# SW6208_A_C_LED__188.net
KiCad netlist of a schematic drawn in Altium Designer
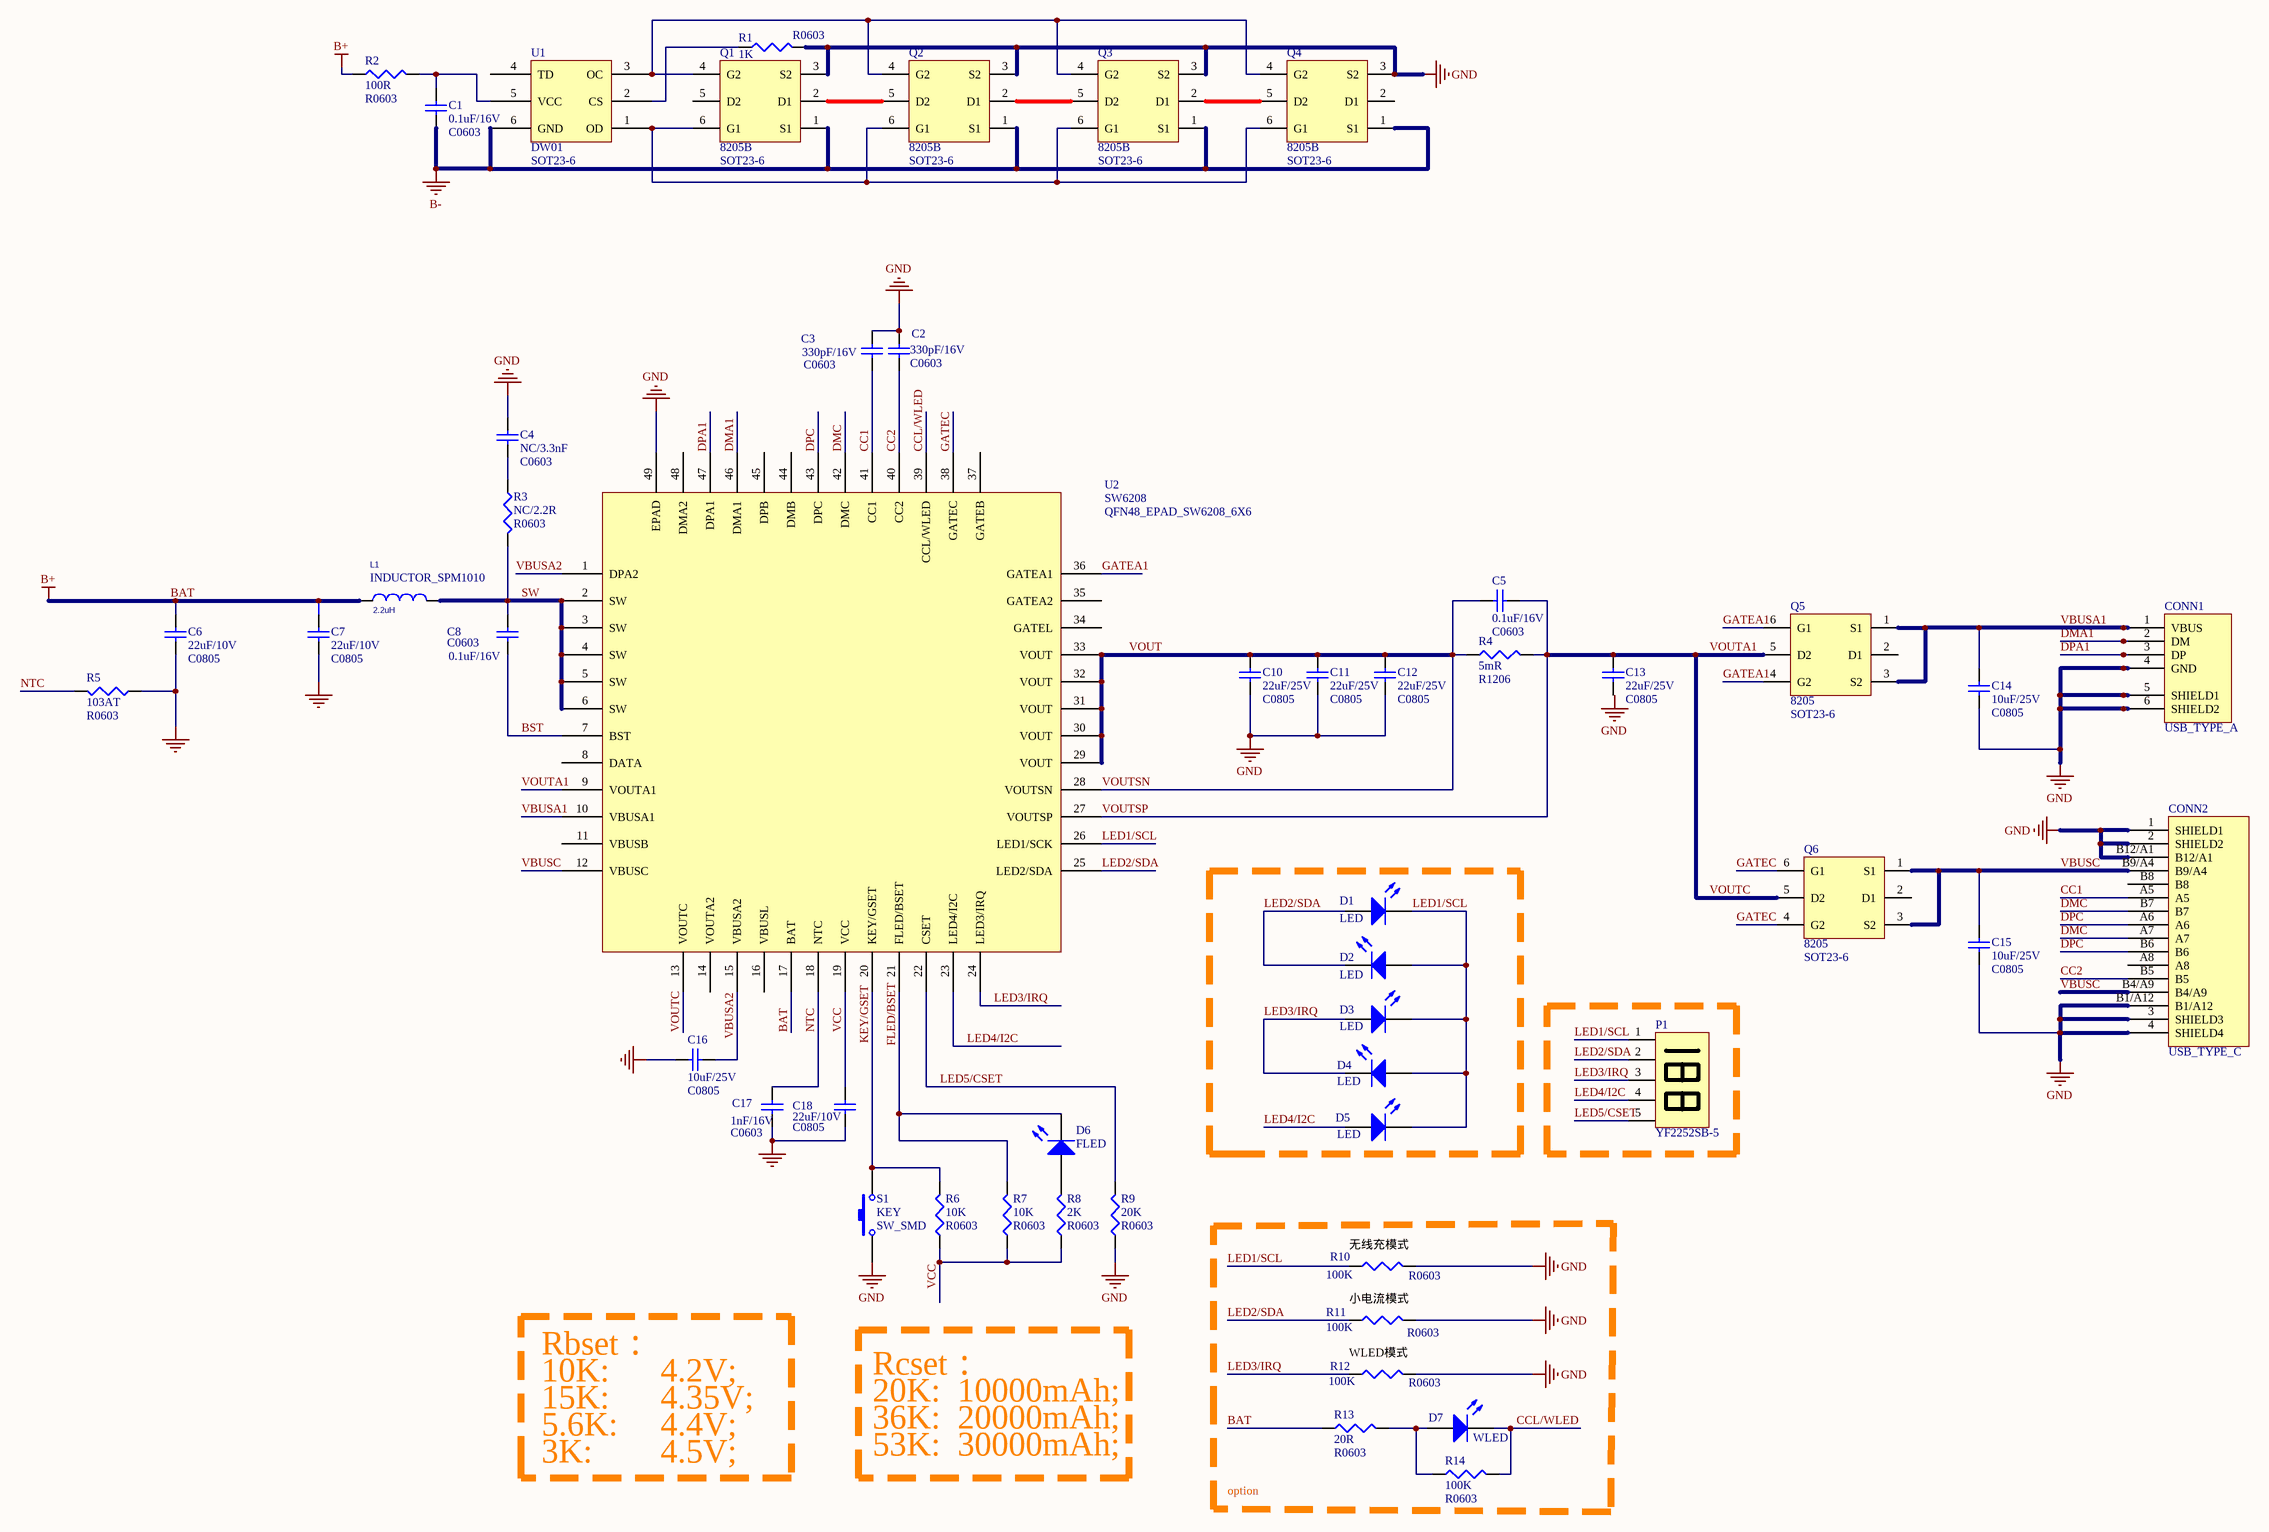
[diagram p0: SW6208+A+C+LED_普通188数码管.SchDoc]

(export (version "E")
  (design (tool "Eeschema 10.0.6"))
  (components
    (comp (ref "C1")
      (value "0.1uF/16V")
      (footprint "C0603")
      (description "Capacitor")
      (fields (field (name "PUBLISHER") "Altium Limited"))
      (libsource (lib "参考设计器件原理图更新") (part "CAP0603"))
    )
    (comp (ref "C2")
      (value "330pF/16V")
      (footprint "C0603")
      (description "Capacitor")
      (fields (field (name "PUBLISHER") "Altium Limited"))
      (libsource (lib "参考设计器件原理图更新") (part "CAP0603"))
    )
    (comp (ref "C3")
      (value "330pF/16V")
      (footprint "C0603")
      (description "Capacitor")
      (fields (field (name "PUBLISHER") "Altium Limited"))
      (libsource (lib "参考设计器件原理图更新") (part "CAP0603"))
    )
    (comp (ref "C4")
      (value "NC/3.3nF")
      (footprint "C0603")
      (description "Capacitor")
      (fields (field (name "PUBLISHER") "Altium Limited"))
      (libsource (lib "参考设计器件原理图更新") (part "CAP0603"))
    )
    (comp (ref "C5")
      (value "0.1uF/16V")
      (footprint "C0603")
      (description "Capacitor")
      (fields (field (name "PUBLISHER") "Altium Limited"))
      (libsource (lib "参考设计器件原理图更新") (part "CAP0603"))
    )
    (comp (ref "C6")
      (value "22uF/10V")
      (footprint "C0805")
      (description "Capacitor")
      (fields (field (name "PUBLISHER") "Altium Limited"))
      (libsource (lib "参考设计器件原理图更新") (part "CAP0805"))
    )
    (comp (ref "C7")
      (value "22uF/10V")
      (footprint "C0805")
      (description "Capacitor")
      (fields (field (name "PUBLISHER") "Altium Limited"))
      (libsource (lib "参考设计器件原理图更新") (part "CAP0805"))
    )
    (comp (ref "C8")
      (value "0.1uF/16V")
      (footprint "C0603")
      (description "Capacitor")
      (fields (field (name "PUBLISHER") "Altium Limited"))
      (libsource (lib "参考设计器件原理图更新") (part "CAP0603"))
    )
    (comp (ref "C10")
      (value "22uF/25V")
      (footprint "C0805")
      (description "Capacitor")
      (fields (field (name "PUBLISHER") "Altium Limited"))
      (libsource (lib "参考设计器件原理图更新") (part "CAP0805"))
    )
    (comp (ref "C11")
      (value "22uF/25V")
      (footprint "C0805")
      (description "Capacitor")
      (fields (field (name "PUBLISHER") "Altium Limited"))
      (libsource (lib "参考设计器件原理图更新") (part "CAP0805"))
    )
    (comp (ref "C12")
      (value "22uF/25V")
      (footprint "C0805")
      (description "Capacitor")
      (fields (field (name "PUBLISHER") "Altium Limited"))
      (libsource (lib "参考设计器件原理图更新") (part "CAP0805"))
    )
    (comp (ref "C13")
      (value "22uF/25V")
      (footprint "C0805")
      (description "Capacitor")
      (fields (field (name "PUBLISHER") "Altium Limited"))
      (libsource (lib "参考设计器件原理图更新") (part "CAP0805"))
    )
    (comp (ref "C14")
      (value "10uF/25V")
      (footprint "C0805")
      (description "Capacitor")
      (fields (field (name "PUBLISHER") "Altium Limited"))
      (libsource (lib "参考设计器件原理图更新") (part "CAP0805"))
    )
    (comp (ref "C15")
      (value "10uF/25V")
      (footprint "C0805")
      (description "Capacitor")
      (fields (field (name "PUBLISHER") "Altium Limited"))
      (libsource (lib "参考设计器件原理图更新") (part "CAP0805"))
    )
    (comp (ref "C16")
      (value "10uF/25V")
      (footprint "C0805")
      (description "Capacitor")
      (fields (field (name "PUBLISHER") "Altium Limited"))
      (libsource (lib "参考设计器件原理图更新") (part "CAP0805"))
    )
    (comp (ref "C17")
      (value "1nF/16V")
      (footprint "C0603")
      (description "Capacitor")
      (fields (field (name "PUBLISHER") "Altium Limited"))
      (libsource (lib "参考设计器件原理图更新") (part "CAP0603"))
    )
    (comp (ref "C18")
      (value "22uF/10V")
      (footprint "C0805")
      (description "Capacitor")
      (fields (field (name "PUBLISHER") "Altium Limited"))
      (libsource (lib "参考设计器件原理图更新") (part "CAP0805"))
    )
    (comp (ref "CONN1")
      (value "USB_TYPE_A")
      (footprint "USB_TYPE_A")
      (libsource (lib "参考设计器件原理图更新") (part "USB_TYPE_A"))
    )
    (comp (ref "CONN2")
      (value "USB_TYPE_C")
      (footprint "LOUISAD:USB_TYPE_C")
      (libsource (lib "参考设计器件原理图更新") (part "USB_TYPE_C"))
    )
    (comp (ref "D1")
      (value "LED")
      (footprint "LED0603")
      (fields (field (name "PUBLISHER") "Altium Limited"))
      (libsource (lib "参考设计器件原理图更新") (part "LED_0603"))
    )
    (comp (ref "D2")
      (value "LED")
      (footprint "LED0603")
      (fields (field (name "PUBLISHER") "Altium Limited"))
      (libsource (lib "参考设计器件原理图更新") (part "LED_0603"))
    )
    (comp (ref "D3")
      (value "LED")
      (footprint "LED0603")
      (fields (field (name "PUBLISHER") "Altium Limited"))
      (libsource (lib "参考设计器件原理图更新") (part "LED_0603"))
    )
    (comp (ref "D4")
      (value "LED")
      (footprint "LED0603")
      (fields (field (name "PUBLISHER") "Altium Limited"))
      (libsource (lib "参考设计器件原理图更新") (part "LED_0603"))
    )
    (comp (ref "D5")
      (value "LED")
      (footprint "LED0603")
      (fields (field (name "PUBLISHER") "Altium Limited"))
      (libsource (lib "参考设计器件原理图更新") (part "LED_0603"))
    )
    (comp (ref "D6")
      (value "FLED")
      (footprint "LED0603")
      (description "LED")
      (fields (field (name "PUBLISHER") "Altium Limited"))
      (libsource (lib "参考设计器件原理图更新") (part "LED_0603"))
    )
    (comp (ref "D7")
      (value "WLED")
      (footprint "LED_5MM")
      (fields (field (name "PUBLISHER") "Altium Limited"))
      (libsource (lib "参考设计器件原理图更新") (part "WLED"))
    )
    (comp (ref "L1")
      (value "2.2uH")
      (footprint "INDUCTOR_SPM1010")
      (description "INDUCTOR")
      (libsource (lib "参考设计器件原理图更新") (part "INDUCTOR_SPM1010"))
    )
    (comp (ref "P1")
      (value "YF2252SB-5")
      (footprint "LED_Display_5")
      (description "188_LED_Display")
      (libsource (lib "参考设计器件原理图更新") (part "LED_Display_5"))
    )
    (comp (ref "Q1")
      (value "8205B")
      (footprint "SOT23-6")
      (description "NMOS")
      (fields (field (name "FOOTPRINF") "SOT23-6"))
      (libsource (lib "参考设计器件原理图更新") (part "8205"))
    )
    (comp (ref "Q2")
      (value "8205B")
      (footprint "SOT23-6")
      (description "NMOS")
      (fields (field (name "FOOTPRINF") "SOT23-6"))
      (libsource (lib "参考设计器件原理图更新") (part "8205"))
    )
    (comp (ref "Q3")
      (value "8205B")
      (footprint "SOT23-6")
      (description "NMOS")
      (fields (field (name "FOOTPRINF") "SOT23-6"))
      (libsource (lib "参考设计器件原理图更新") (part "8205"))
    )
    (comp (ref "Q4")
      (value "8205B")
      (footprint "SOT23-6")
      (description "NMOS")
      (fields (field (name "FOOTPRINF") "SOT23-6"))
      (libsource (lib "参考设计器件原理图更新") (part "8205"))
    )
    (comp (ref "Q5")
      (value "8205")
      (footprint "SOT23-6")
      (description "NMOS")
      (fields (field (name "FOOTPRINF") "SOT23-6"))
      (libsource (lib "") (part "8205_1"))
    )
    (comp (ref "Q6")
      (value "8205")
      (footprint "SOT23-6")
      (description "NMOS")
      (fields (field (name "FOOTPRINF") "SOT23-6"))
      (libsource (lib "") (part "8205_1"))
    )
    (comp (ref "R1")
      (value "1K")
      (footprint "R0603")
      (description "Resistor")
      (fields (field (name "PUBLISHER") "Altium Limited"))
      (libsource (lib "参考设计器件原理图更新") (part "RES_0603"))
    )
    (comp (ref "R2")
      (value "100R")
      (footprint "R0603")
      (description "Resistor")
      (fields (field (name "PUBLISHER") "Altium Limited"))
      (libsource (lib "参考设计器件原理图更新") (part "RES_0603"))
    )
    (comp (ref "R3")
      (value "NC/2.2R")
      (footprint "R0603")
      (description "Resistor")
      (fields (field (name "PUBLISHER") "Altium Limited"))
      (libsource (lib "参考设计器件原理图更新") (part "RES_0603"))
    )
    (comp (ref "R4")
      (value "5mR")
      (footprint "R1206")
      (description "Resistor")
      (fields (field (name "PUBLISHER") "Altium Limited"))
      (libsource (lib "参考设计器件原理图更新") (part "RES_1206"))
    )
    (comp (ref "R5")
      (value "103AT")
      (footprint "R0603")
      (description "Resistor")
      (fields (field (name "PUBLISHER") "Altium Limited"))
      (libsource (lib "参考设计器件原理图更新") (part "RES_0603"))
    )
    (comp (ref "R6")
      (value "10K")
      (footprint "R0603")
      (description "Resistor")
      (fields (field (name "PUBLISHER") "Altium Limited"))
      (libsource (lib "参考设计器件原理图更新") (part "RES_0603"))
    )
    (comp (ref "R7")
      (value "10K")
      (footprint "R0603")
      (description "Resistor")
      (fields (field (name "PUBLISHER") "Altium Limited"))
      (libsource (lib "参考设计器件原理图更新") (part "RES_0603"))
    )
    (comp (ref "R8")
      (value "2K")
      (footprint "R0603")
      (description "Resistor")
      (fields (field (name "PUBLISHER") "Altium Limited"))
      (libsource (lib "参考设计器件原理图更新") (part "RES_0603"))
    )
    (comp (ref "R9")
      (value "20K")
      (footprint "R0603")
      (description "Resistor")
      (fields (field (name "PUBLISHER") "Altium Limited"))
      (libsource (lib "参考设计器件原理图更新") (part "RES_0603"))
    )
    (comp (ref "R10")
      (value "100K")
      (footprint "R0603")
      (description "Resistor")
      (fields (field (name "PUBLISHER") "Altium Limited"))
      (libsource (lib "参考设计器件原理图更新") (part "RES_0603"))
    )
    (comp (ref "R11")
      (value "100K")
      (footprint "R0603")
      (description "Resistor")
      (fields (field (name "PUBLISHER") "Altium Limited"))
      (libsource (lib "参考设计器件原理图更新") (part "RES_0603"))
    )
    (comp (ref "R12")
      (value "100K")
      (footprint "R0603")
      (description "Resistor")
      (fields (field (name "PUBLISHER") "Altium Limited"))
      (libsource (lib "参考设计器件原理图更新") (part "RES_0603"))
    )
    (comp (ref "R13")
      (value "20R")
      (footprint "R0603")
      (description "Resistor")
      (fields (field (name "PUBLISHER") "Altium Limited"))
      (libsource (lib "参考设计器件原理图更新") (part "RES_0603"))
    )
    (comp (ref "R14")
      (value "100K")
      (footprint "R0603")
      (description "Resistor")
      (fields (field (name "PUBLISHER") "Altium Limited"))
      (libsource (lib "参考设计器件原理图更新") (part "RES_0603"))
    )
    (comp (ref "S1")
      (value "KEY")
      (footprint "SW_SMD")
      (fields (field (name "FOOTPRINF") "SW_SMD"))
      (libsource (lib "参考设计器件原理图更新") (part "SW K"))
    )
    (comp (ref "U1")
      (value "DW01")
      (footprint "SOT23-6")
      (description "BAT_PROTECT_IC")
      (libsource (lib "参考设计器件原理图更新") (part "DW01"))
    )
    (comp (ref "U2")
      (value "SW6208")
      (footprint "QFN48_EPAD_SW6208_6X6")
      (description "IC")
      (libsource (lib "芯片型号原理图") (part "SW6208"))
    )
  )
  (nets
    (net (code "1") (name "/BST") (class "Default")
      (node (ref "C8") (pin "1") (pinfunction "1_1") (pintype "passive"))
      (node (ref "U2") (pin "7") (pinfunction "BST_7") (pintype "passive"))
    )
    (net (code "2") (name "/CC1") (class "Default")
      (node (ref "C3") (pin "1") (pinfunction "1_1") (pintype "passive"))
      (node (ref "CONN2") (pin "A5") (pinfunction "A5_A5") (pintype "passive"))
      (node (ref "U2") (pin "41") (pinfunction "CC1_41") (pintype "passive"))
    )
    (net (code "3") (name "/CC2") (class "Default")
      (node (ref "C2") (pin "1") (pinfunction "1_1") (pintype "passive"))
      (node (ref "CONN2") (pin "B5") (pinfunction "B5_B5") (pintype "passive"))
      (node (ref "U2") (pin "40") (pinfunction "CC2_40") (pintype "passive"))
    )
    (net (code "4") (name "/CCL{slash}WLED") (class "Default")
      (node (ref "D7") (pin "2") (pinfunction "K_2") (pintype "passive"))
      (node (ref "R14") (pin "2") (pinfunction "2_2") (pintype "passive"))
      (node (ref "U2") (pin "39") (pinfunction "CCL/WLED_39") (pintype "passive"))
    )
    (net (code "5") (name "/DMA1") (class "Default")
      (node (ref "CONN1") (pin "2") (pinfunction "DM_2") (pintype "passive"))
      (node (ref "U2") (pin "46") (pinfunction "DMA1_46") (pintype "passive"))
    )
    (net (code "6") (name "/DMC") (class "Default")
      (node (ref "CONN2") (pin "A7") (pinfunction "A7_A7") (pintype "passive"))
      (node (ref "CONN2") (pin "B7") (pinfunction "B7_B7") (pintype "passive"))
      (node (ref "U2") (pin "42") (pinfunction "DMC_42") (pintype "passive"))
    )
    (net (code "7") (name "/DPA1") (class "Default")
      (node (ref "CONN1") (pin "3") (pinfunction "DP_3") (pintype "passive"))
      (node (ref "U2") (pin "47") (pinfunction "DPA1_47") (pintype "passive"))
    )
    (net (code "8") (name "/DPC") (class "Default")
      (node (ref "CONN2") (pin "A6") (pinfunction "A6_A6") (pintype "passive"))
      (node (ref "CONN2") (pin "B6") (pinfunction "B6_B6") (pintype "passive"))
      (node (ref "U2") (pin "43") (pinfunction "DPC_43") (pintype "passive"))
    )
    (net (code "9") (name "/FLED{slash}BSET") (class "Default")
      (node (ref "D6") (pin "2") (pinfunction "K_2") (pintype "passive"))
      (node (ref "R7") (pin "2") (pinfunction "2_2") (pintype "passive"))
      (node (ref "U2") (pin "21") (pinfunction "FLED/BSET_21") (pintype "passive"))
    )
    (net (code "10") (name "/GATEA1") (class "Default")
      (node (ref "Q5") (pin "4") (pinfunction "G2_4") (pintype "passive"))
      (node (ref "Q5") (pin "6") (pinfunction "G1_6") (pintype "passive"))
      (node (ref "U2") (pin "36") (pinfunction "GATEA1_36") (pintype "passive"))
    )
    (net (code "11") (name "/GATEC") (class "Default")
      (node (ref "Q6") (pin "4") (pinfunction "G2_4") (pintype "passive"))
      (node (ref "Q6") (pin "6") (pinfunction "G1_6") (pintype "passive"))
      (node (ref "U2") (pin "38") (pinfunction "GATEC_38") (pintype "passive"))
    )
    (net (code "12") (name "/KEY{slash}GSET") (class "Default")
      (node (ref "R6") (pin "2") (pinfunction "2_2") (pintype "passive"))
      (node (ref "S1") (pin "2") (pinfunction "2_2") (pintype "passive"))
      (node (ref "U2") (pin "20") (pinfunction "KEY/GSET_20") (pintype "passive"))
    )
    (net (code "13") (name "/LED1{slash}SCL") (class "Default")
      (node (ref "D1") (pin "2") (pinfunction "K_2") (pintype "passive"))
      (node (ref "D2") (pin "1") (pinfunction "A_1") (pintype "passive"))
      (node (ref "D3") (pin "2") (pinfunction "K_2") (pintype "passive"))
      (node (ref "D4") (pin "1") (pinfunction "A_1") (pintype "passive"))
      (node (ref "D5") (pin "2") (pinfunction "K_2") (pintype "passive"))
      (node (ref "P1") (pin "1") (pinfunction "F_1") (pintype "passive"))
      (node (ref "R10") (pin "1") (pinfunction "1_1") (pintype "passive"))
      (node (ref "U2") (pin "26") (pinfunction "LED1/SCK_26") (pintype "passive"))
    )
    (net (code "14") (name "/LED2{slash}SDA") (class "Default")
      (node (ref "D1") (pin "1") (pinfunction "A_1") (pintype "passive"))
      (node (ref "D2") (pin "2") (pinfunction "K_2") (pintype "passive"))
      (node (ref "P1") (pin "2") (pinfunction "C_2") (pintype "passive"))
      (node (ref "R11") (pin "1") (pinfunction "1_1") (pintype "passive"))
      (node (ref "U2") (pin "25") (pinfunction "LED2/SDA_25") (pintype "passive"))
    )
    (net (code "15") (name "/LED3{slash}IRQ") (class "Default")
      (node (ref "D3") (pin "1") (pinfunction "A_1") (pintype "passive"))
      (node (ref "D4") (pin "2") (pinfunction "K_2") (pintype "passive"))
      (node (ref "P1") (pin "3") (pinfunction "D_3") (pintype "passive"))
      (node (ref "R12") (pin "1") (pinfunction "1_1") (pintype "passive"))
      (node (ref "U2") (pin "24") (pinfunction "LED3/IRQ_24") (pintype "passive"))
    )
    (net (code "16") (name "/LED4{slash}I2C") (class "Default")
      (node (ref "D5") (pin "1") (pinfunction "A_1") (pintype "passive"))
      (node (ref "P1") (pin "4") (pinfunction "E_4") (pintype "passive"))
      (node (ref "U2") (pin "23") (pinfunction "LED4/I2C_23") (pintype "passive"))
    )
    (net (code "17") (name "/LED5{slash}CSET") (class "Default")
      (node (ref "P1") (pin "5") (pinfunction "G_5") (pintype "passive"))
      (node (ref "R9") (pin "2") (pinfunction "2_2") (pintype "passive"))
      (node (ref "U2") (pin "22") (pinfunction "CSET_22") (pintype "passive"))
    )
    (net (code "18") (name "/NTC") (class "Default")
      (node (ref "C17") (pin "1") (pinfunction "1_1") (pintype "passive"))
      (node (ref "R5") (pin "2") (pinfunction "2_2") (pintype "passive"))
      (node (ref "U2") (pin "18") (pinfunction "NTC_18") (pintype "passive"))
    )
    (net (code "19") (name "/SW") (class "Default")
      (node (ref "C8") (pin "2") (pinfunction "2_2") (pintype "passive"))
      (node (ref "L1") (pin "2") (pinfunction "2_2") (pintype "passive"))
      (node (ref "R3") (pin "2") (pinfunction "2_2") (pintype "passive"))
      (node (ref "U2") (pin "2") (pinfunction "SW_2") (pintype "passive"))
      (node (ref "U2") (pin "3") (pinfunction "SW_3") (pintype "passive"))
      (node (ref "U2") (pin "4") (pinfunction "SW_4") (pintype "passive"))
      (node (ref "U2") (pin "5") (pinfunction "SW_5") (pintype "passive"))
      (node (ref "U2") (pin "6") (pinfunction "SW_6") (pintype "passive"))
    )
    (net (code "20") (name "/VBUSA1") (class "Default")
      (node (ref "C14") (pin "2") (pinfunction "2_2") (pintype "passive"))
      (node (ref "CONN1") (pin "1") (pinfunction "VBUS_1") (pintype "passive"))
      (node (ref "Q5") (pin "1") (pinfunction "S1_1") (pintype "passive"))
      (node (ref "Q5") (pin "3") (pinfunction "S2_3") (pintype "passive"))
      (node (ref "U2") (pin "10") (pinfunction "VBUSA1_10") (pintype "passive"))
    )
    (net (code "21") (name "/VBUSA2") (class "Default")
      (node (ref "C16") (pin "2") (pinfunction "2_2") (pintype "passive"))
      (node (ref "U2") (pin "1") (pinfunction "DPA2_1") (pintype "passive"))
      (node (ref "U2") (pin "15") (pinfunction "VBUSA2_15") (pintype "passive"))
    )
    (net (code "22") (name "/VBUSC") (class "Default")
      (node (ref "C15") (pin "2") (pinfunction "2_2") (pintype "passive"))
      (node (ref "CONN2") (pin "B4/A9") (pinfunction "B4/A9_B4/A9") (pintype "passive"))
      (node (ref "CONN2") (pin "B9/A4") (pinfunction "B9/A4_B9/A4") (pintype "passive"))
      (node (ref "Q6") (pin "1") (pinfunction "S1_1") (pintype "passive"))
      (node (ref "Q6") (pin "3") (pinfunction "S2_3") (pintype "passive"))
      (node (ref "U2") (pin "12") (pinfunction "VBUSC_12") (pintype "passive"))
    )
    (net (code "23") (name "/VCC") (class "Default")
      (node (ref "C18") (pin "1") (pinfunction "1_1") (pintype "passive"))
      (node (ref "R6") (pin "1") (pinfunction "1_1") (pintype "passive"))
      (node (ref "R7") (pin "1") (pinfunction "1_1") (pintype "passive"))
      (node (ref "R8") (pin "1") (pinfunction "1_1") (pintype "passive"))
      (node (ref "U2") (pin "19") (pinfunction "VCC_19") (pintype "passive"))
    )
    (net (code "24") (name "/VOUT") (class "Default")
      (node (ref "C10") (pin "2") (pinfunction "2_2") (pintype "passive"))
      (node (ref "C11") (pin "2") (pinfunction "2_2") (pintype "passive"))
      (node (ref "C12") (pin "2") (pinfunction "2_2") (pintype "passive"))
      (node (ref "C5") (pin "1") (pinfunction "1_1") (pintype "passive"))
      (node (ref "R4") (pin "1") (pinfunction "1_1") (pintype "passive"))
      (node (ref "U2") (pin "28") (pinfunction "VOUTSN_28") (pintype "passive"))
      (node (ref "U2") (pin "29") (pinfunction "VOUT_29") (pintype "passive"))
      (node (ref "U2") (pin "30") (pinfunction "VOUT_30") (pintype "passive"))
      (node (ref "U2") (pin "31") (pinfunction "VOUT_31") (pintype "passive"))
      (node (ref "U2") (pin "32") (pinfunction "VOUT_32") (pintype "passive"))
      (node (ref "U2") (pin "33") (pinfunction "VOUT_33") (pintype "passive"))
    )
    (net (code "25") (name "/VOUTA1") (class "Default")
      (node (ref "C13") (pin "2") (pinfunction "2_2") (pintype "passive"))
      (node (ref "C5") (pin "2") (pinfunction "2_2") (pintype "passive"))
      (node (ref "Q5") (pin "5") (pinfunction "D2_5") (pintype "passive"))
      (node (ref "Q6") (pin "5") (pinfunction "D2_5") (pintype "passive"))
      (node (ref "R4") (pin "2") (pinfunction "2_2") (pintype "passive"))
      (node (ref "U2") (pin "13") (pinfunction "VOUTC_13") (pintype "passive"))
      (node (ref "U2") (pin "27") (pinfunction "VOUTSP_27") (pintype "passive"))
      (node (ref "U2") (pin "9") (pinfunction "VOUTA1_9") (pintype "passive"))
    )
    (net (code "26") (name "B+") (class "Default")
      (node (ref "C6") (pin "2") (pinfunction "2_2") (pintype "passive"))
      (node (ref "C7") (pin "2") (pinfunction "2_2") (pintype "passive"))
      (node (ref "L1") (pin "1") (pinfunction "1_1") (pintype "passive"))
      (node (ref "R13") (pin "1") (pinfunction "1_1") (pintype "passive"))
      (node (ref "R2") (pin "1") (pinfunction "1_1") (pintype "passive"))
      (node (ref "U2") (pin "17") (pinfunction "BAT_17") (pintype "passive"))
    )
    (net (code "27") (name "B-") (class "Default")
      (node (ref "C1") (pin "1") (pinfunction "1_1") (pintype "passive"))
      (node (ref "Q1") (pin "1") (pinfunction "S1_1") (pintype "passive"))
      (node (ref "Q2") (pin "1") (pinfunction "S1_1") (pintype "passive"))
      (node (ref "Q3") (pin "1") (pinfunction "S1_1") (pintype "passive"))
      (node (ref "Q4") (pin "1") (pinfunction "S1_1") (pintype "passive"))
      (node (ref "U1") (pin "6") (pinfunction "GND_6") (pintype "passive"))
    )
    (net (code "28") (name "GND") (class "Default")
      (node (ref "C10") (pin "1") (pinfunction "1_1") (pintype "passive"))
      (node (ref "C11") (pin "1") (pinfunction "1_1") (pintype "passive"))
      (node (ref "C12") (pin "1") (pinfunction "1_1") (pintype "passive"))
      (node (ref "C14") (pin "1") (pinfunction "1_1") (pintype "passive"))
      (node (ref "C15") (pin "1") (pinfunction "1_1") (pintype "passive"))
      (node (ref "C16") (pin "1") (pinfunction "1_1") (pintype "passive"))
      (node (ref "C17") (pin "2") (pinfunction "2_2") (pintype "passive"))
      (node (ref "C18") (pin "2") (pinfunction "2_2") (pintype "passive"))
      (node (ref "C2") (pin "2") (pinfunction "2_2") (pintype "passive"))
      (node (ref "C3") (pin "2") (pinfunction "2_2") (pintype "passive"))
      (node (ref "C4") (pin "2") (pinfunction "2_2") (pintype "passive"))
      (node (ref "C6") (pin "1") (pinfunction "1_1") (pintype "passive"))
      (node (ref "C7") (pin "1") (pinfunction "1_1") (pintype "passive"))
      (node (ref "CONN1") (pin "4") (pinfunction "GND_4") (pintype "passive"))
      (node (ref "CONN1") (pin "5") (pinfunction "SHIELD1_5") (pintype "passive"))
      (node (ref "CONN1") (pin "6") (pinfunction "SHIELD2_6") (pintype "passive"))
      (node (ref "CONN2") (pin "1") (pinfunction "SHIELD1_1") (pintype "passive"))
      (node (ref "CONN2") (pin "2") (pinfunction "SHIELD2_2") (pintype "passive"))
      (node (ref "CONN2") (pin "3") (pinfunction "SHIELD3_3") (pintype "passive"))
      (node (ref "CONN2") (pin "4") (pinfunction "SHIELD4_4") (pintype "passive"))
      (node (ref "CONN2") (pin "B1/A12") (pinfunction "B1/A12_B1/A12") (pintype "passive"))
      (node (ref "CONN2") (pin "B12/A1") (pinfunction "B12/A1_B12/A1") (pintype "passive"))
      (node (ref "Q1") (pin "3") (pinfunction "S2_3") (pintype "passive"))
      (node (ref "Q2") (pin "3") (pinfunction "S2_3") (pintype "passive"))
      (node (ref "Q3") (pin "3") (pinfunction "S2_3") (pintype "passive"))
      (node (ref "Q4") (pin "3") (pinfunction "S2_3") (pintype "passive"))
      (node (ref "R1") (pin "2") (pinfunction "2_2") (pintype "passive"))
      (node (ref "R10") (pin "2") (pinfunction "2_2") (pintype "passive"))
      (node (ref "R11") (pin "2") (pinfunction "2_2") (pintype "passive"))
      (node (ref "R12") (pin "2") (pinfunction "2_2") (pintype "passive"))
      (node (ref "R5") (pin "1") (pinfunction "1_1") (pintype "passive"))
      (node (ref "R9") (pin "1") (pinfunction "1_1") (pintype "passive"))
      (node (ref "S1") (pin "1") (pinfunction "1_1") (pintype "passive"))
      (node (ref "U2") (pin "49") (pinfunction "EPAD_49") (pintype "passive"))
    )
    (net (code "29") (name "Net-(C4-Pad1)") (class "Default")
      (node (ref "C4") (pin "1") (pinfunction "1_1") (pintype "passive"))
      (node (ref "R3") (pin "1") (pinfunction "1_1") (pintype "passive"))
    )
    (net (code "30") (name "Net-(D6-A)") (class "Default")
      (node (ref "D6") (pin "1") (pinfunction "A_1") (pintype "passive"))
      (node (ref "R8") (pin "2") (pinfunction "2_2") (pintype "passive"))
    )
    (net (code "31") (name "Net-(D7-A)") (class "Default")
      (node (ref "D7") (pin "1") (pinfunction "A_1") (pintype "passive"))
      (node (ref "R13") (pin "2") (pinfunction "2_2") (pintype "passive"))
      (node (ref "R14") (pin "1") (pinfunction "1_1") (pintype "passive"))
    )
    (net (code "32") (name "Net-(Q1-D1)") (class "Default")
      (node (ref "Q1") (pin "2") (pinfunction "D1_2") (pintype "passive"))
      (node (ref "Q2") (pin "5") (pinfunction "D2_5") (pintype "passive"))
    )
    (net (code "33") (name "Net-(Q1-G1)") (class "Default")
      (node (ref "Q1") (pin "6") (pinfunction "G1_6") (pintype "passive"))
      (node (ref "Q2") (pin "6") (pinfunction "G1_6") (pintype "passive"))
      (node (ref "Q3") (pin "6") (pinfunction "G1_6") (pintype "passive"))
      (node (ref "Q4") (pin "6") (pinfunction "G1_6") (pintype "passive"))
      (node (ref "U1") (pin "1") (pinfunction "OD_1") (pintype "passive"))
    )
    (net (code "34") (name "Net-(Q1-G2)") (class "Default")
      (node (ref "Q1") (pin "4") (pinfunction "G2_4") (pintype "passive"))
      (node (ref "Q2") (pin "4") (pinfunction "G2_4") (pintype "passive"))
      (node (ref "Q3") (pin "4") (pinfunction "G2_4") (pintype "passive"))
      (node (ref "Q4") (pin "4") (pinfunction "G2_4") (pintype "passive"))
      (node (ref "U1") (pin "3") (pinfunction "OC_3") (pintype "passive"))
    )
    (net (code "35") (name "Net-(Q2-D1)") (class "Default")
      (node (ref "Q2") (pin "2") (pinfunction "D1_2") (pintype "passive"))
      (node (ref "Q3") (pin "5") (pinfunction "D2_5") (pintype "passive"))
    )
    (net (code "36") (name "Net-(Q3-D1)") (class "Default")
      (node (ref "Q3") (pin "2") (pinfunction "D1_2") (pintype "passive"))
      (node (ref "Q4") (pin "5") (pinfunction "D2_5") (pintype "passive"))
    )
    (net (code "37") (name "Net-(U1-CS)") (class "Default")
      (node (ref "R1") (pin "1") (pinfunction "1_1") (pintype "passive"))
      (node (ref "U1") (pin "2") (pinfunction "CS_2") (pintype "passive"))
    )
    (net (code "38") (name "Net-(U1-VCC)") (class "Default")
      (node (ref "C1") (pin "2") (pinfunction "2_2") (pintype "passive"))
      (node (ref "R2") (pin "2") (pinfunction "2_2") (pintype "passive"))
      (node (ref "U1") (pin "5") (pinfunction "VCC_5") (pintype "passive"))
    )
    (net (code "39") (name "unconnected-(C13-Pad1)") (class "Default")
      (node (ref "C13") (pin "1") (pinfunction "1_1") (pintype "passive"))
    )
    (net (code "40") (name "unconnected-(CONN2-PadA8)") (class "Default")
      (node (ref "CONN2") (pin "A8") (pinfunction "A8_A8") (pintype "passive"))
    )
    (net (code "41") (name "unconnected-(CONN2-PadB8)") (class "Default")
      (node (ref "CONN2") (pin "B8") (pinfunction "B8_B8") (pintype "passive"))
    )
    (net (code "42") (name "unconnected-(Q1-D2-Pad5)") (class "Default")
      (node (ref "Q1") (pin "5") (pinfunction "D2_5") (pintype "passive"))
    )
    (net (code "43") (name "unconnected-(Q4-D1-Pad2)") (class "Default")
      (node (ref "Q4") (pin "2") (pinfunction "D1_2") (pintype "passive"))
    )
    (net (code "44") (name "unconnected-(Q5-D1-Pad2)") (class "Default")
      (node (ref "Q5") (pin "2") (pinfunction "D1_2") (pintype "passive"))
    )
    (net (code "45") (name "unconnected-(Q6-D1-Pad2)") (class "Default")
      (node (ref "Q6") (pin "2") (pinfunction "D1_2") (pintype "passive"))
    )
    (net (code "46") (name "unconnected-(U1-TD-Pad4)") (class "Default")
      (node (ref "U1") (pin "4") (pinfunction "TD_4") (pintype "passive"))
    )
    (net (code "47") (name "unconnected-(U2-DATA-Pad8)") (class "Default")
      (node (ref "U2") (pin "8") (pinfunction "DATA_8") (pintype "passive"))
    )
    (net (code "48") (name "unconnected-(U2-DMA2-Pad48)") (class "Default")
      (node (ref "U2") (pin "48") (pinfunction "DMA2_48") (pintype "passive"))
    )
    (net (code "49") (name "unconnected-(U2-DMB-Pad44)") (class "Default")
      (node (ref "U2") (pin "44") (pinfunction "DMB_44") (pintype "passive"))
    )
    (net (code "50") (name "unconnected-(U2-DPB-Pad45)") (class "Default")
      (node (ref "U2") (pin "45") (pinfunction "DPB_45") (pintype "passive"))
    )
    (net (code "51") (name "unconnected-(U2-GATEA2-Pad35)") (class "Default")
      (node (ref "U2") (pin "35") (pinfunction "GATEA2_35") (pintype "passive"))
    )
    (net (code "52") (name "unconnected-(U2-GATEB-Pad37)") (class "Default")
      (node (ref "U2") (pin "37") (pinfunction "GATEB_37") (pintype "passive"))
    )
    (net (code "53") (name "unconnected-(U2-GATEL-Pad34)") (class "Default")
      (node (ref "U2") (pin "34") (pinfunction "GATEL_34") (pintype "passive"))
    )
    (net (code "54") (name "unconnected-(U2-VBUSB-Pad11)") (class "Default")
      (node (ref "U2") (pin "11") (pinfunction "VBUSB_11") (pintype "passive"))
    )
    (net (code "55") (name "unconnected-(U2-VBUSL-Pad16)") (class "Default")
      (node (ref "U2") (pin "16") (pinfunction "VBUSL_16") (pintype "passive"))
    )
    (net (code "56") (name "unconnected-(U2-VOUTA2-Pad14)") (class "Default")
      (node (ref "U2") (pin "14") (pinfunction "VOUTA2_14") (pintype "passive"))
    )
  )
)
